# Delay_Line.net
KiCad netlist of a schematic drawn in Altium Designer
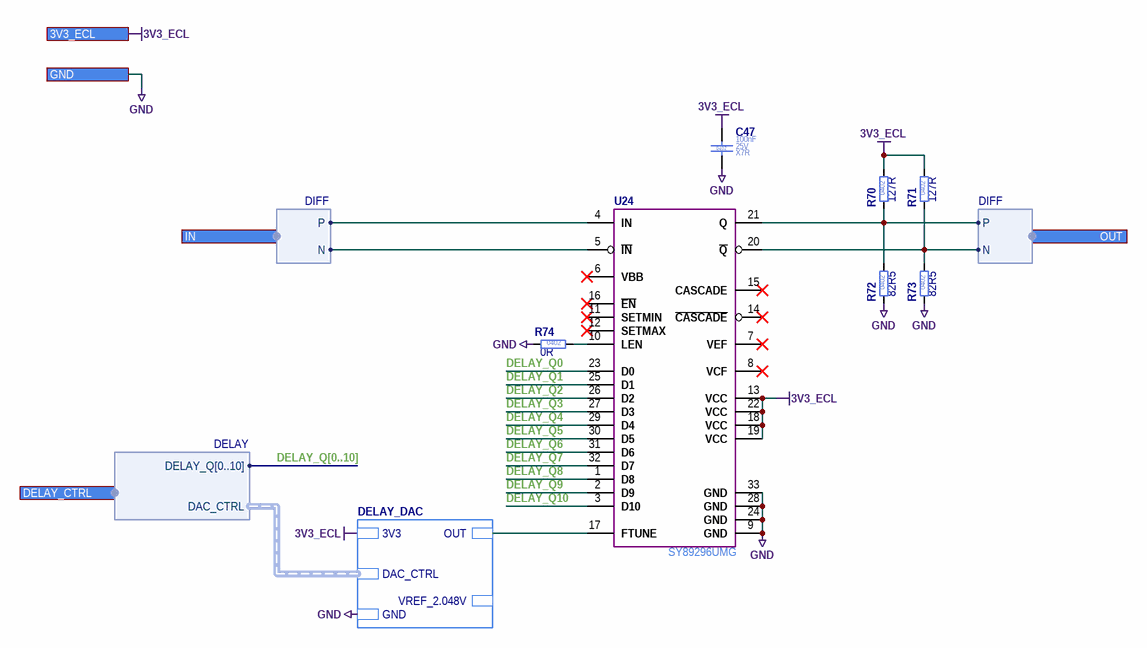
[diagram p0: Delay_Line.SchDoc]

(export (version "E")
  (design (tool "Eeschema 10.0.6"))
  (components
    (comp (ref "C47")
      (value "C_100NF_25V_X7R_0402_10")
      (footprint "C_0402_1005")
      (description "Ceramic Capacitor")
      (fields
        (field (name "CASE/PACKAGE") "0402")
        (field (name "VOLTAGE RATING (DC)") "25V")
        (field (name "DIELECTRIC") "X7R")
        (field (name "CAPACITANCE") "100nF")
        (field (name "TOLERANCE") "10%")
        (field (name "MANUFACTURER PART NUMBER") "EMK105B7104KV-F")
      )
      (libsource (lib "7Sigma") (part "C"))
    )
    (comp (ref "R70")
      (value "R_127R_0402_1")
      (footprint "R_0402_1005")
      (description "Thick Film Resistor")
      (fields
        (field (name "RESISTANCE") "127R")
        (field (name "CASE/PACKAGE") "0402")
        (field (name "TOLERANCE") "1%")
        (field (name "MANUFACTURER") "Yageo")
      )
      (libsource (lib "7Sigma") (part "R"))
    )
    (comp (ref "R71")
      (value "R_127R_0402_1")
      (footprint "R_0402_1005")
      (description "Thick Film Resistor")
      (fields
        (field (name "RESISTANCE") "127R")
        (field (name "CASE/PACKAGE") "0402")
        (field (name "TOLERANCE") "1%")
        (field (name "MANUFACTURER") "Yageo")
      )
      (libsource (lib "7Sigma") (part "R"))
    )
    (comp (ref "R72")
      (value "R_82R5_0402_1")
      (footprint "R_0402_1005")
      (description "Thick Film Resistor")
      (fields
        (field (name "RESISTANCE") "82R5")
        (field (name "CASE/PACKAGE") "0402")
        (field (name "TOLERANCE") "1%")
        (field (name "MANUFACTURER") "Yageo")
      )
      (libsource (lib "7Sigma") (part "R"))
    )
    (comp (ref "R73")
      (value "R_82R5_0402_1")
      (footprint "R_0402_1005")
      (description "Thick Film Resistor")
      (fields
        (field (name "RESISTANCE") "82R5")
        (field (name "CASE/PACKAGE") "0402")
        (field (name "TOLERANCE") "1%")
        (field (name "MANUFACTURER") "Yageo")
      )
      (libsource (lib "7Sigma") (part "R"))
    )
    (comp (ref "R74")
      (value "R_0R_0402_1")
      (footprint "R_0402_1005")
      (description "Thick Film Resistor")
      (fields
        (field (name "RESISTANCE") "0R")
        (field (name "CASE/PACKAGE") "0402")
        (field (name "TOLERANCE") "1%")
        (field (name "MANUFACTURER") "Yageo")
      )
      (libsource (lib "7Sigma") (part "R"))
    )
    (comp (ref "U24")
      (value "SY89296UMG")
      (footprint "QFN50P500X500X100_HS-33N")
      (description "Delay Lines/Timing Elements 2.5V/3.3V PECL Delay Line")
      (fields
        (field (name "MANUFACTURER") "Microchip")
        (field (name "MANUFACTURER PART NUMBER") "SY89296UMG")
      )
      (libsource (lib "7Sigma") (part "SY89296U"))
    )
  )
  (nets
    (net (code "5") (name "/DELAY_Q0") (class "Default")
      (node (ref "U24") (pin "23") (pinfunction "D0_23") (pintype "passive"))
    )
    (net (code "6") (name "/DELAY_Q1") (class "Default")
      (node (ref "U24") (pin "25") (pinfunction "D1_25") (pintype "passive"))
    )
    (net (code "7") (name "/DELAY_Q2") (class "Default")
      (node (ref "U24") (pin "26") (pinfunction "D2_26") (pintype "passive"))
    )
    (net (code "8") (name "/DELAY_Q3") (class "Default")
      (node (ref "U24") (pin "27") (pinfunction "D3_27") (pintype "passive"))
    )
    (net (code "9") (name "/DELAY_Q4") (class "Default")
      (node (ref "U24") (pin "29") (pinfunction "D4_29") (pintype "passive"))
    )
    (net (code "10") (name "/DELAY_Q5") (class "Default")
      (node (ref "U24") (pin "30") (pinfunction "D5_30") (pintype "passive"))
    )
    (net (code "11") (name "/DELAY_Q6") (class "Default")
      (node (ref "U24") (pin "31") (pinfunction "D6_31") (pintype "passive"))
    )
    (net (code "12") (name "/DELAY_Q7") (class "Default")
      (node (ref "U24") (pin "32") (pinfunction "D7_32") (pintype "passive"))
    )
    (net (code "13") (name "/DELAY_Q8") (class "Default")
      (node (ref "U24") (pin "1") (pinfunction "D8_1") (pintype "passive"))
    )
    (net (code "14") (name "/DELAY_Q9") (class "Default")
      (node (ref "U24") (pin "2") (pinfunction "D9_2") (pintype "passive"))
    )
    (net (code "15") (name "/DELAY_Q10") (class "Default")
      (node (ref "U24") (pin "3") (pinfunction "D10_3") (pintype "passive"))
    )
    (net (code "17") (name "/OUT") (class "Default")
      (node (ref "U24") (pin "17") (pinfunction "FTUNE_17") (pintype "passive"))
    )
    (net (code "21") (name "3V3_ECL") (class "Default")
      (node (ref "C47") (pin "1") (pinfunction "1_1") (pintype "passive"))
      (node (ref "R70") (pin "2") (pinfunction "2_2") (pintype "passive"))
      (node (ref "R71") (pin "2") (pinfunction "2_2") (pintype "passive"))
      (node (ref "U24") (pin "13") (pinfunction "VCC_13") (pintype "passive"))
      (node (ref "U24") (pin "18") (pinfunction "VCC_18") (pintype "passive"))
      (node (ref "U24") (pin "19") (pinfunction "VCC_19") (pintype "passive"))
      (node (ref "U24") (pin "22") (pinfunction "VCC_22") (pintype "passive"))
    )
    (net (code "22") (name "GND") (class "Default")
      (node (ref "C47") (pin "2") (pinfunction "2_2") (pintype "passive"))
      (node (ref "R72") (pin "1") (pinfunction "1_1") (pintype "passive"))
      (node (ref "R73") (pin "1") (pinfunction "1_1") (pintype "passive"))
      (node (ref "R74") (pin "1") (pinfunction "1_1") (pintype "passive"))
      (node (ref "U24") (pin "24") (pinfunction "GND_24") (pintype "passive"))
      (node (ref "U24") (pin "28") (pinfunction "GND_28") (pintype "passive"))
      (node (ref "U24") (pin "33") (pinfunction "GND_33") (pintype "passive"))
      (node (ref "U24") (pin "9") (pinfunction "GND_9") (pintype "passive"))
    )
    (net (code "23") (name "Net-(R70-Pad1)") (class "Default")
      (node (ref "R70") (pin "1") (pinfunction "1_1") (pintype "passive"))
      (node (ref "R72") (pin "2") (pinfunction "2_2") (pintype "passive"))
      (node (ref "U24") (pin "21") (pinfunction "Q_21") (pintype "passive"))
    )
    (net (code "24") (name "Net-(R71-Pad1)") (class "Default")
      (node (ref "R71") (pin "1") (pinfunction "1_1") (pintype "passive"))
      (node (ref "R73") (pin "2") (pinfunction "2_2") (pintype "passive"))
      (node (ref "U24") (pin "20") (pinfunction "Q_20") (pintype "passive"))
    )
    (net (code "25") (name "Net-(U24-LEN)") (class "Default")
      (node (ref "R74") (pin "2") (pinfunction "2_2") (pintype "passive"))
      (node (ref "U24") (pin "10") (pinfunction "LEN_10") (pintype "passive"))
    )
    (net (code "26") (name "unconnected-(U24-CASCADE-Pad14)") (class "Default")
      (node (ref "U24") (pin "14") (pinfunction "CASCADE_14") (pintype "passive+no_connect"))
    )
    (net (code "27") (name "unconnected-(U24-CASCADE-Pad15)") (class "Default")
      (node (ref "U24") (pin "15") (pinfunction "CASCADE_15") (pintype "passive+no_connect"))
    )
    (net (code "28") (name "unconnected-(U24-EN-Pad16)") (class "Default")
      (node (ref "U24") (pin "16") (pinfunction "EN_16") (pintype "passive+no_connect"))
    )
    (net (code "29") (name "unconnected-(U24-IN-Pad4)") (class "Default")
      (node (ref "U24") (pin "4") (pinfunction "IN_4") (pintype "passive"))
    )
    (net (code "30") (name "unconnected-(U24-IN-Pad5)") (class "Default")
      (node (ref "U24") (pin "5") (pinfunction "IN_5") (pintype "passive"))
    )
    (net (code "31") (name "unconnected-(U24-SETMAX-Pad12)") (class "Default")
      (node (ref "U24") (pin "12") (pinfunction "SETMAX_12") (pintype "passive+no_connect"))
    )
    (net (code "32") (name "unconnected-(U24-SETMIN-Pad11)") (class "Default")
      (node (ref "U24") (pin "11") (pinfunction "SETMIN_11") (pintype "passive+no_connect"))
    )
    (net (code "33") (name "unconnected-(U24-VBB-Pad6)") (class "Default")
      (node (ref "U24") (pin "6") (pinfunction "VBB_6") (pintype "passive+no_connect"))
    )
    (net (code "34") (name "unconnected-(U24-VCF-Pad8)") (class "Default")
      (node (ref "U24") (pin "8") (pinfunction "VCF_8") (pintype "passive+no_connect"))
    )
    (net (code "35") (name "unconnected-(U24-VEF-Pad7)") (class "Default")
      (node (ref "U24") (pin "7") (pinfunction "VEF_7") (pintype "passive+no_connect"))
    )
  )
)
